# Z.net
KiCad netlist of a schematic drawn in Altium Designer
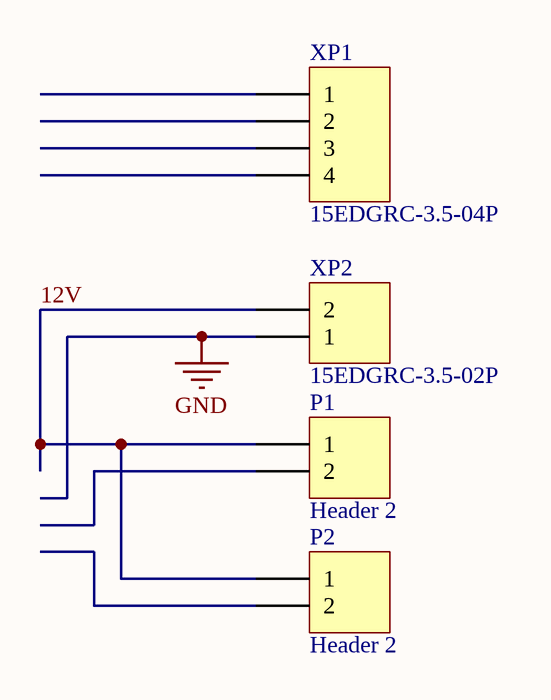
[diagram p0: Z.SchDoc]

(export (version "E")
  (design (tool "Eeschema 10.0.6"))
  (components
    (comp (ref "P1")
      (value "Header 2")
      (footprint "HDR1X2")
      (description "Header, 2-Pin")
      (fields (field (name "PUBLISHER") "Altium Limited"))
      (libsource (lib "Miscellaneous Connectors") (part "Header 2"))
    )
    (comp (ref "P2")
      (value "Header 2")
      (footprint "HDR1X2")
      (description "Header, 2-Pin")
      (fields (field (name "PUBLISHER") "Altium Limited"))
      (libsource (lib "Miscellaneous Connectors") (part "Header 2"))
    )
    (comp (ref "XP1")
      (value "15EDGRC-3.5-04P")
      (footprint "RR_CONN_15EDGRC-3.5-04P")
      (description "CONN 15EDGRC-3.5-04P R-HEADER")
      (fields (field (name "MANUFACTURER") "DEGSON ELECTRONICS"))
      (libsource (lib "RozumLibrary") (part "15EDGRC-3.5-04P"))
    )
    (comp (ref "XP2")
      (value "15EDGRC-3.5-02P")
      (footprint "RR_CONN_15EDGRC-3.5-02P")
      (description "CONN 15EDGRC-3.5-02P R-HEADER")
      (fields (field (name "MANUFACTURER") "DEGSON ELECTRONICS"))
      (libsource (lib "RozumLibrary") (part "15EDGRC-3.5-02P"))
    )
  )
  (nets
    (net (code "1") (name "/12V") (class "Default")
      (node (ref "P1") (pin "1") (pinfunction "1_1") (pintype "passive"))
      (node (ref "P2") (pin "1") (pinfunction "1_1") (pintype "passive"))
      (node (ref "XP2") (pin "2") (pinfunction "2_2") (pintype "passive"))
    )
    (net (code "2") (name "GND") (class "Default")
      (node (ref "XP2") (pin "1") (pinfunction "1_1") (pintype "passive"))
    )
    (net (code "3") (name "unconnected-(P1-Pad2)") (class "Default")
      (node (ref "P1") (pin "2") (pinfunction "2_2") (pintype "passive"))
    )
    (net (code "4") (name "unconnected-(P2-Pad2)") (class "Default")
      (node (ref "P2") (pin "2") (pinfunction "2_2") (pintype "passive"))
    )
    (net (code "5") (name "unconnected-(XP1-Pad1)") (class "Default")
      (node (ref "XP1") (pin "1") (pinfunction "1_1") (pintype "passive"))
    )
    (net (code "6") (name "unconnected-(XP1-Pad2)") (class "Default")
      (node (ref "XP1") (pin "2") (pinfunction "2_2") (pintype "passive"))
    )
    (net (code "7") (name "unconnected-(XP1-Pad3)") (class "Default")
      (node (ref "XP1") (pin "3") (pinfunction "3_3") (pintype "passive"))
    )
    (net (code "8") (name "unconnected-(XP1-Pad4)") (class "Default")
      (node (ref "XP1") (pin "4") (pinfunction "4_4") (pintype "passive"))
    )
  )
)
